# Reference_Design.net
KiCad netlist of a schematic drawn in EAGLE
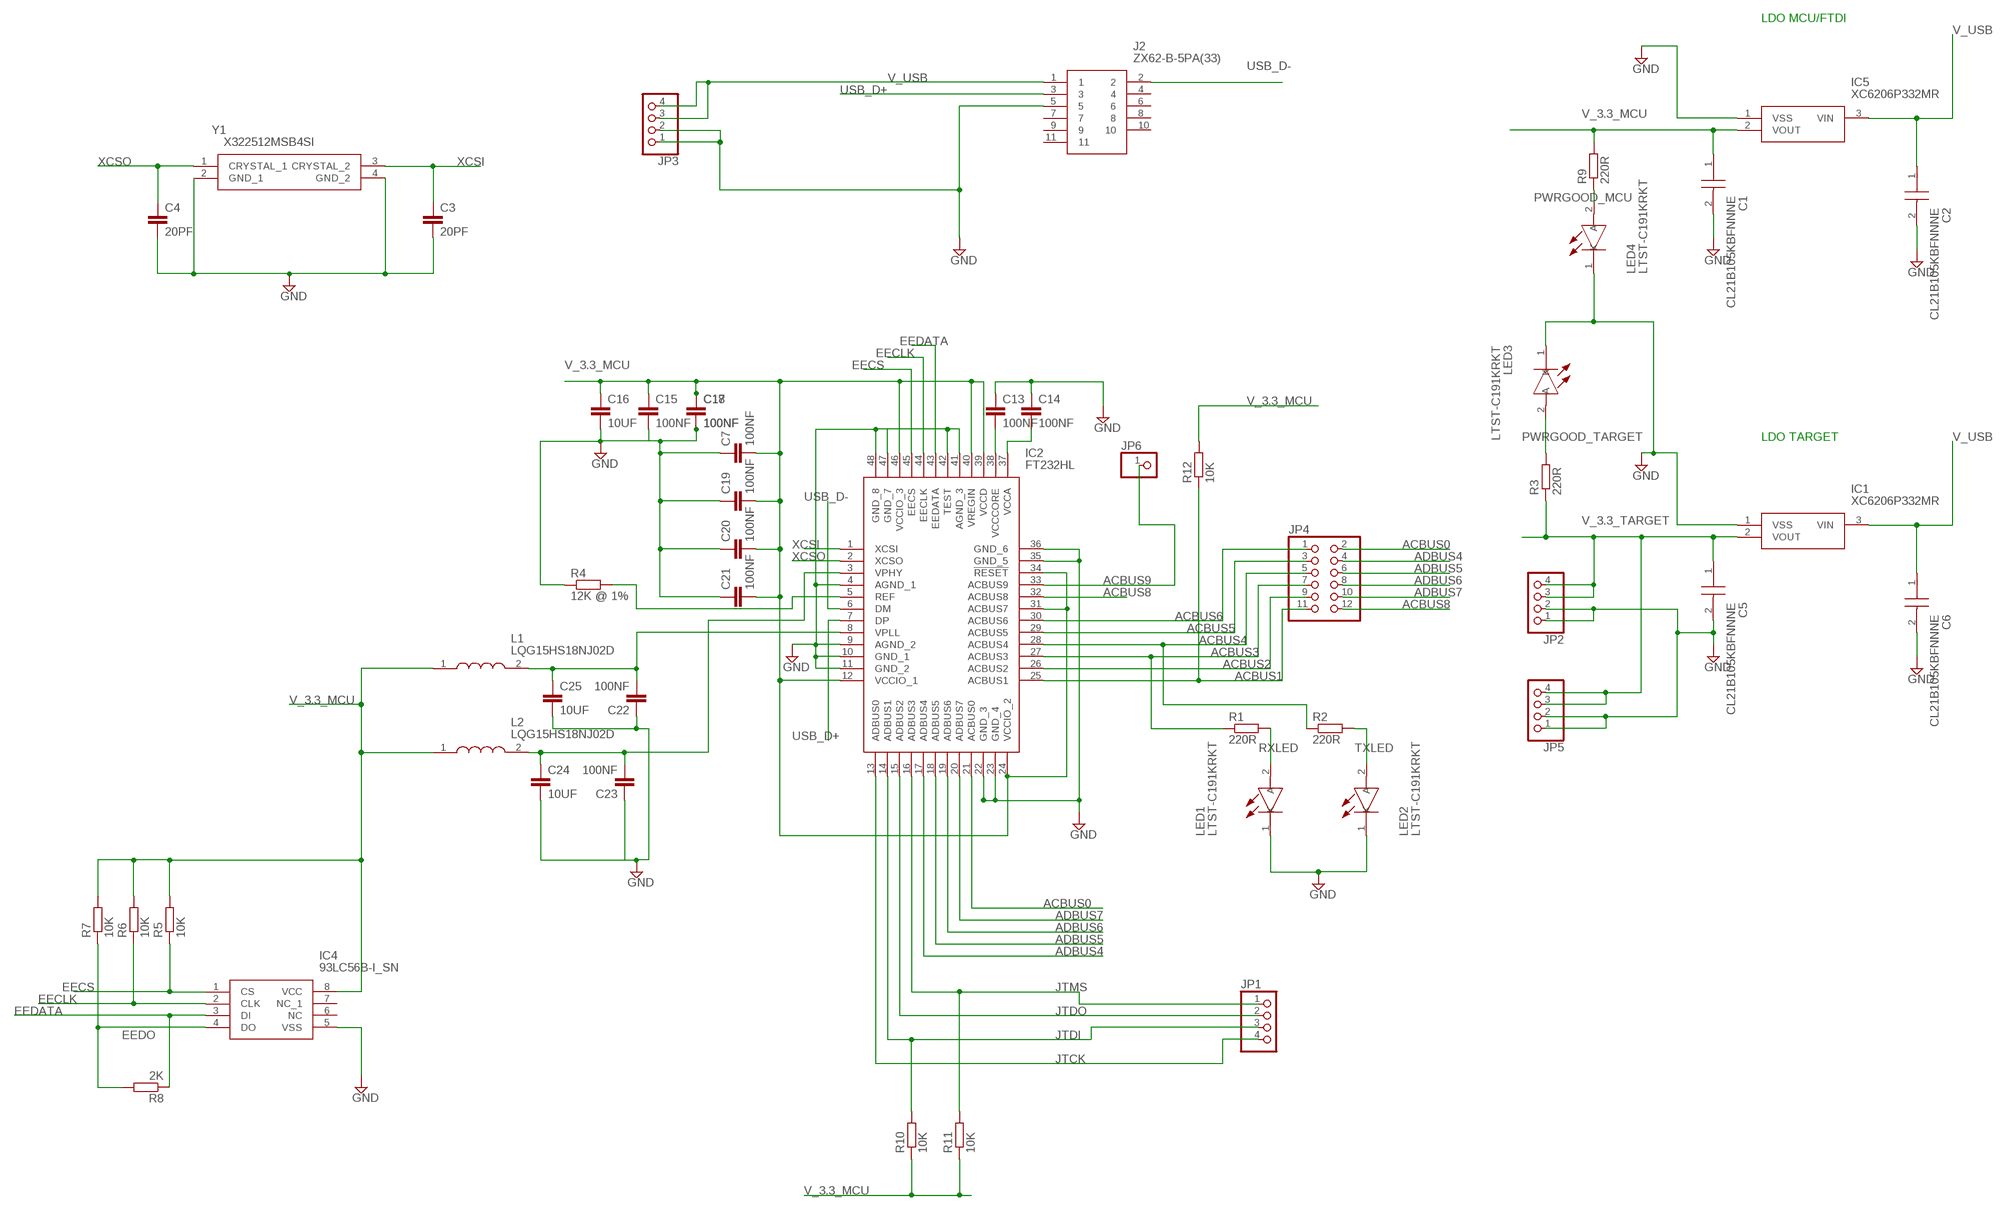
[diagram p0: schematic, sheet 1]

(export (version "E")
  (design (tool "Eeschema 10.0.6"))
  (components
    (comp (ref "C1")
      (value "CL21B105KBFNNNE")
      (footprint "eagle-import:CAPC2012X135N")
      (libsource (lib "eagle-import") (part "CL21B105KBFNNNE"))
    )
    (comp (ref "C2")
      (value "CL21B105KBFNNNE")
      (footprint "eagle-import:CAPC2012X135N")
      (libsource (lib "eagle-import") (part "CL21B105KBFNNNE"))
    )
    (comp (ref "C3")
      (value "20PF")
      (footprint "eagle-import:C0603")
      (libsource (lib "eagle-import") (part "C-EUC0603"))
    )
    (comp (ref "C4")
      (value "20PF")
      (footprint "eagle-import:C0603")
      (libsource (lib "eagle-import") (part "C-EUC0603"))
    )
    (comp (ref "C5")
      (value "CL21B105KBFNNNE")
      (footprint "eagle-import:CAPC2012X135N")
      (libsource (lib "eagle-import") (part "CL21B105KBFNNNE"))
    )
    (comp (ref "C6")
      (value "CL21B105KBFNNNE")
      (footprint "eagle-import:CAPC2012X135N")
      (libsource (lib "eagle-import") (part "CL21B105KBFNNNE"))
    )
    (comp (ref "C7")
      (value "100NF")
      (footprint "eagle-import:C0603")
      (libsource (lib "eagle-import") (part "C-EUC0603"))
    )
    (comp (ref "C13")
      (value "100NF")
      (footprint "eagle-import:C0603")
      (libsource (lib "eagle-import") (part "C-EUC0603"))
    )
    (comp (ref "C14")
      (value "100NF")
      (footprint "eagle-import:C0603")
      (libsource (lib "eagle-import") (part "C-EUC0603"))
    )
    (comp (ref "C15")
      (value "100NF")
      (footprint "eagle-import:C0603")
      (libsource (lib "eagle-import") (part "C-EUC0603"))
    )
    (comp (ref "C16")
      (value "10UF")
      (footprint "eagle-import:C1206")
      (libsource (lib "eagle-import") (part "C-EUC1206"))
    )
    (comp (ref "C17")
      (value "100NF")
      (footprint "eagle-import:C0603")
      (libsource (lib "eagle-import") (part "C-EUC0603"))
    )
    (comp (ref "C18")
      (value "100NF")
      (footprint "eagle-import:C0603")
      (libsource (lib "eagle-import") (part "C-EUC0603"))
    )
    (comp (ref "C19")
      (value "100NF")
      (footprint "eagle-import:C0603")
      (libsource (lib "eagle-import") (part "C-EUC0603"))
    )
    (comp (ref "C20")
      (value "100NF")
      (footprint "eagle-import:C0603")
      (libsource (lib "eagle-import") (part "C-EUC0603"))
    )
    (comp (ref "C21")
      (value "100NF")
      (footprint "eagle-import:C0603")
      (libsource (lib "eagle-import") (part "C-EUC0603"))
    )
    (comp (ref "C22")
      (value "100NF")
      (footprint "eagle-import:C0603")
      (libsource (lib "eagle-import") (part "C-EUC0603"))
    )
    (comp (ref "C23")
      (value "100NF")
      (footprint "eagle-import:C0603")
      (libsource (lib "eagle-import") (part "C-EUC0603"))
    )
    (comp (ref "C24")
      (value "10UF")
      (footprint "eagle-import:C1206")
      (libsource (lib "eagle-import") (part "C-EUC1206"))
    )
    (comp (ref "C25")
      (value "10UF")
      (footprint "eagle-import:C1206")
      (libsource (lib "eagle-import") (part "C-EUC1206"))
    )
    (comp (ref "IC1")
      (value "XC6206P332MR")
      (footprint "eagle-import:SOT95P280X130-3N")
      (libsource (lib "eagle-import") (part "XC6206P332MR"))
    )
    (comp (ref "IC2")
      (value "FT232HL")
      (footprint "eagle-import:QFP50P900X900X160-48N")
      (fields
        (field (name "MANUFACTURER_PART_NUMBER") "FT232HL-REEL")
        (field (name "MOUSER_PART_NUMBER") "895-FT232HL-REEL")
        (field (name "RS_PART_NUMBER") "7377843P")
      )
      (libsource (lib "eagle-import") (part "FT232HL-REEL"))
    )
    (comp (ref "IC4")
      (value "93LC56B-I_SN")
      (footprint "eagle-import:SOIC127P600X175-8N")
      (fields
        (field (name "MANUFACTURER_PART_NUMBER") "93LC56B-I/SN")
        (field (name "MOUSER_PART_NUMBER") "579-93LC56BISN")
        (field (name "RS_PART_NUMBER") "0454347P")
      )
      (libsource (lib "eagle-import") (part "93LC56B-I_SN"))
    )
    (comp (ref "IC5")
      (value "XC6206P332MR")
      (footprint "eagle-import:SOT95P280X130-3N")
      (libsource (lib "eagle-import") (part "XC6206P332MR"))
    )
    (comp (ref "J2")
      (value "ZX62-B-5PA(33)")
      (footprint "eagle-import:ZX62B5PA33")
      (fields
        (field (name "MOUSER_PART_NUMBER") "798-ZX62-B-5PA33")
        (field (name "RS_PART_NUMBER") "1362267")
      )
      (libsource (lib "eagle-import") (part "ZX62-B-5PA(33)"))
    )
    (comp (ref "JP1")
      (value "PINHD-1X4")
      (footprint "eagle-import:1X04")
      (libsource (lib "eagle-import") (part "PINHD-1X4"))
    )
    (comp (ref "JP2")
      (value "PINHD-1X4")
      (footprint "eagle-import:1X04")
      (libsource (lib "eagle-import") (part "PINHD-1X4"))
    )
    (comp (ref "JP3")
      (value "PINHD-1X4")
      (footprint "eagle-import:1X04")
      (libsource (lib "eagle-import") (part "PINHD-1X4"))
    )
    (comp (ref "JP4")
      (value "PINHD-2X6")
      (footprint "eagle-import:2X06")
      (libsource (lib "eagle-import") (part "PINHD-2X6"))
    )
    (comp (ref "JP5")
      (value "PINHD-1X4")
      (footprint "eagle-import:1X04")
      (libsource (lib "eagle-import") (part "PINHD-1X4"))
    )
    (comp (ref "JP6")
      (value "PINHD-1X1")
      (footprint "eagle-import:1X01")
      (libsource (lib "eagle-import") (part "PINHD-1X1"))
    )
    (comp (ref "L1")
      (value "LQG15HS18NJ02D")
      (footprint "eagle-import:INDC1005X55N")
      (fields
        (field (name "MOUSER_PART_NUMBER") "81-LQG15HS18NJ02D")
        (field (name "RS_PART_NUMBER") "7254910")
      )
      (libsource (lib "eagle-import") (part "LQG15HS18NJ02D"))
    )
    (comp (ref "L2")
      (value "LQG15HS18NJ02D")
      (footprint "eagle-import:INDC1005X55N")
      (fields
        (field (name "MOUSER_PART_NUMBER") "81-LQG15HS18NJ02D")
        (field (name "RS_PART_NUMBER") "7254910")
      )
      (libsource (lib "eagle-import") (part "LQG15HS18NJ02D"))
    )
    (comp (ref "LED1")
      (value "LTST-C191KRKT")
      (footprint "eagle-import:LEDC1608X55N")
      (fields
        (field (name "MOUSER_PART_NUMBER") "859-LTST-C191KRKT")
        (field (name "RS_PART_NUMBER") "1278415P")
      )
      (libsource (lib "eagle-import") (part "LTST-C191KRKT"))
    )
    (comp (ref "LED2")
      (value "LTST-C191KRKT")
      (footprint "eagle-import:LEDC1608X55N")
      (fields
        (field (name "MOUSER_PART_NUMBER") "859-LTST-C191KRKT")
        (field (name "RS_PART_NUMBER") "1278415P")
      )
      (libsource (lib "eagle-import") (part "LTST-C191KRKT"))
    )
    (comp (ref "LED3")
      (value "LTST-C191KRKT")
      (footprint "eagle-import:LEDC1608X55N")
      (fields
        (field (name "MOUSER_PART_NUMBER") "859-LTST-C191KRKT")
        (field (name "RS_PART_NUMBER") "1278415P")
      )
      (libsource (lib "eagle-import") (part "LTST-C191KRKT"))
    )
    (comp (ref "LED4")
      (value "LTST-C191KRKT")
      (footprint "eagle-import:LEDC1608X55N")
      (fields
        (field (name "MOUSER_PART_NUMBER") "859-LTST-C191KRKT")
        (field (name "RS_PART_NUMBER") "1278415P")
      )
      (libsource (lib "eagle-import") (part "LTST-C191KRKT"))
    )
    (comp (ref "R1")
      (value "220R")
      (footprint "eagle-import:R0603")
      (libsource (lib "eagle-import") (part "R-EU_R0603"))
    )
    (comp (ref "R2")
      (value "220R")
      (footprint "eagle-import:R0603")
      (libsource (lib "eagle-import") (part "R-EU_R0603"))
    )
    (comp (ref "R3")
      (value "220R")
      (footprint "eagle-import:R0603")
      (libsource (lib "eagle-import") (part "R-EU_R0603"))
    )
    (comp (ref "R4")
      (value "12K @ 1%")
      (footprint "eagle-import:R0603")
      (libsource (lib "eagle-import") (part "R-EU_R0603"))
    )
    (comp (ref "R5")
      (value "10K")
      (footprint "eagle-import:R1206")
      (libsource (lib "eagle-import") (part "R-EU_R1206"))
    )
    (comp (ref "R6")
      (value "10K")
      (footprint "eagle-import:R1206")
      (libsource (lib "eagle-import") (part "R-EU_R1206"))
    )
    (comp (ref "R7")
      (value "10K")
      (footprint "eagle-import:R1206")
      (libsource (lib "eagle-import") (part "R-EU_R1206"))
    )
    (comp (ref "R8")
      (value "2K")
      (footprint "eagle-import:R1206")
      (libsource (lib "eagle-import") (part "R-EU_R1206"))
    )
    (comp (ref "R9")
      (value "220R")
      (footprint "eagle-import:R0603")
      (libsource (lib "eagle-import") (part "R-EU_R0603"))
    )
    (comp (ref "R10")
      (value "10K")
      (footprint "eagle-import:R1206")
      (libsource (lib "eagle-import") (part "R-EU_R1206"))
    )
    (comp (ref "R11")
      (value "10K")
      (footprint "eagle-import:R1206")
      (libsource (lib "eagle-import") (part "R-EU_R1206"))
    )
    (comp (ref "R12")
      (value "10K")
      (footprint "eagle-import:R1206")
      (libsource (lib "eagle-import") (part "R-EU_R1206"))
    )
    (comp (ref "Y1")
      (value "X322512MSB4SI")
      (footprint "eagle-import:X322512MSB4SI")
      (libsource (lib "eagle-import") (part "X322512MSB4SI"))
    )
  )
  (nets
    (net (code "1") (name "/ACBUS0") (class "Default")
      (node (ref "IC2") (pin "21") (pinfunction "ACBUS0_21") (pintype "bidirectional"))
      (node (ref "JP4") (pin "2") (pinfunction "2_2") (pintype "passive"))
    )
    (net (code "2") (name "/ACBUS1") (class "Default")
      (node (ref "IC2") (pin "25") (pinfunction "ACBUS1_25") (pintype "bidirectional"))
      (node (ref "JP4") (pin "11") (pinfunction "11_11") (pintype "passive"))
      (node (ref "R12") (pin "1") (pinfunction "1_1") (pintype "passive"))
    )
    (net (code "3") (name "/ACBUS2") (class "Default")
      (node (ref "IC2") (pin "26") (pinfunction "ACBUS2_26") (pintype "bidirectional"))
      (node (ref "JP4") (pin "9") (pinfunction "9_9") (pintype "passive"))
    )
    (net (code "4") (name "/ACBUS3") (class "Default")
      (node (ref "IC2") (pin "27") (pinfunction "ACBUS3_27") (pintype "bidirectional"))
      (node (ref "JP4") (pin "7") (pinfunction "7_7") (pintype "passive"))
      (node (ref "R1") (pin "1") (pinfunction "1_1") (pintype "passive"))
    )
    (net (code "5") (name "/ACBUS4") (class "Default")
      (node (ref "IC2") (pin "28") (pinfunction "ACBUS4_28") (pintype "bidirectional"))
      (node (ref "JP4") (pin "5") (pinfunction "5_5") (pintype "passive"))
      (node (ref "R2") (pin "1") (pinfunction "1_1") (pintype "passive"))
    )
    (net (code "6") (name "/ACBUS5") (class "Default")
      (node (ref "IC2") (pin "29") (pinfunction "ACBUS5_29") (pintype "bidirectional"))
      (node (ref "JP4") (pin "3") (pinfunction "3_3") (pintype "passive"))
    )
    (net (code "7") (name "/ACBUS6") (class "Default")
      (node (ref "IC2") (pin "30") (pinfunction "ACBUS6_30") (pintype "bidirectional"))
      (node (ref "JP4") (pin "1") (pinfunction "1_1") (pintype "passive"))
    )
    (net (code "8") (name "/ACBUS8") (class "Default")
      (node (ref "IC2") (pin "32") (pinfunction "ACBUS8_32") (pintype "bidirectional"))
      (node (ref "JP4") (pin "12") (pinfunction "12_12") (pintype "passive"))
    )
    (net (code "9") (name "/ACBUS9") (class "Default")
      (node (ref "IC2") (pin "33") (pinfunction "ACBUS9_33") (pintype "bidirectional"))
      (node (ref "JP6") (pin "1") (pinfunction "1_1") (pintype "passive"))
    )
    (net (code "10") (name "/ADBUS4") (class "Default")
      (node (ref "IC2") (pin "17") (pinfunction "ADBUS4_17") (pintype "bidirectional"))
      (node (ref "JP4") (pin "4") (pinfunction "4_4") (pintype "passive"))
    )
    (net (code "11") (name "/ADBUS5") (class "Default")
      (node (ref "IC2") (pin "18") (pinfunction "ADBUS5_18") (pintype "bidirectional"))
      (node (ref "JP4") (pin "6") (pinfunction "6_6") (pintype "passive"))
    )
    (net (code "12") (name "/ADBUS6") (class "Default")
      (node (ref "IC2") (pin "19") (pinfunction "ADBUS6_19") (pintype "bidirectional"))
      (node (ref "JP4") (pin "8") (pinfunction "8_8") (pintype "passive"))
    )
    (net (code "13") (name "/ADBUS7") (class "Default")
      (node (ref "IC2") (pin "20") (pinfunction "ADBUS7_20") (pintype "bidirectional"))
      (node (ref "JP4") (pin "10") (pinfunction "10_10") (pintype "passive"))
    )
    (net (code "14") (name "/EECLK") (class "Default")
      (node (ref "IC2") (pin "44") (pinfunction "EECLK_44") (pintype "input"))
      (node (ref "IC4") (pin "2") (pinfunction "CLK_2") (pintype "input"))
      (node (ref "R6") (pin "1") (pinfunction "1_1") (pintype "passive"))
    )
    (net (code "15") (name "/EECS") (class "Default")
      (node (ref "IC2") (pin "45") (pinfunction "EECS_45") (pintype "input"))
      (node (ref "IC4") (pin "1") (pinfunction "CS_1") (pintype "input"))
      (node (ref "R5") (pin "1") (pinfunction "1_1") (pintype "passive"))
    )
    (net (code "16") (name "/EEDATA") (class "Default")
      (node (ref "IC2") (pin "43") (pinfunction "EEDATA_43") (pintype "bidirectional"))
      (node (ref "IC4") (pin "3") (pinfunction "DI_3") (pintype "bidirectional"))
      (node (ref "R8") (pin "1") (pinfunction "1_1") (pintype "passive"))
    )
    (net (code "17") (name "/EEDO") (class "Default")
      (node (ref "IC4") (pin "4") (pinfunction "DO_4") (pintype "bidirectional"))
      (node (ref "R7") (pin "1") (pinfunction "1_1") (pintype "passive"))
      (node (ref "R8") (pin "2") (pinfunction "2_2") (pintype "passive"))
    )
    (net (code "18") (name "/JTCK") (class "Default")
      (node (ref "IC2") (pin "13") (pinfunction "ADBUS0_13") (pintype "bidirectional"))
      (node (ref "JP1") (pin "4") (pinfunction "4_4") (pintype "passive"))
    )
    (net (code "19") (name "/JTDI") (class "Default")
      (node (ref "IC2") (pin "14") (pinfunction "ADBUS1_14") (pintype "bidirectional"))
      (node (ref "JP1") (pin "3") (pinfunction "3_3") (pintype "passive"))
      (node (ref "R10") (pin "2") (pinfunction "2_2") (pintype "passive"))
    )
    (net (code "20") (name "/JTDO") (class "Default")
      (node (ref "IC2") (pin "15") (pinfunction "ADBUS2_15") (pintype "bidirectional"))
      (node (ref "JP1") (pin "2") (pinfunction "2_2") (pintype "passive"))
    )
    (net (code "21") (name "/JTMS") (class "Default")
      (node (ref "IC2") (pin "16") (pinfunction "ADBUS3_16") (pintype "bidirectional"))
      (node (ref "JP1") (pin "1") (pinfunction "1_1") (pintype "passive"))
      (node (ref "R11") (pin "2") (pinfunction "2_2") (pintype "passive"))
    )
    (net (code "22") (name "/PWRGOOD_MCU") (class "Default")
      (node (ref "LED4") (pin "2") (pinfunction "A_2") (pintype "bidirectional"))
      (node (ref "R9") (pin "1") (pinfunction "1_1") (pintype "passive"))
    )
    (net (code "23") (name "/PWRGOOD_TARGET") (class "Default")
      (node (ref "LED3") (pin "2") (pinfunction "A_2") (pintype "bidirectional"))
      (node (ref "R3") (pin "2") (pinfunction "2_2") (pintype "passive"))
    )
    (net (code "24") (name "/RXLED") (class "Default")
      (node (ref "LED1") (pin "2") (pinfunction "A_2") (pintype "bidirectional"))
      (node (ref "R1") (pin "2") (pinfunction "2_2") (pintype "passive"))
    )
    (net (code "25") (name "/TXLED") (class "Default")
      (node (ref "LED2") (pin "2") (pinfunction "A_2") (pintype "bidirectional"))
      (node (ref "R2") (pin "2") (pinfunction "2_2") (pintype "passive"))
    )
    (net (code "26") (name "/USB_D+") (class "Default")
      (node (ref "IC2") (pin "7") (pinfunction "DP_7") (pintype "bidirectional"))
      (node (ref "J2") (pin "3") (pinfunction "3_3") (pintype "bidirectional"))
    )
    (net (code "27") (name "/USB_D-") (class "Default")
      (node (ref "IC2") (pin "6") (pinfunction "DM_6") (pintype "bidirectional"))
      (node (ref "J2") (pin "2") (pinfunction "2_2") (pintype "bidirectional"))
    )
    (net (code "28") (name "/V_3.3_MCU") (class "Default")
      (node (ref "C1") (pin "1") (pinfunction "1_1") (pintype "bidirectional"))
      (node (ref "C15") (pin "1") (pinfunction "1_1") (pintype "passive"))
      (node (ref "C16") (pin "1") (pinfunction "1_1") (pintype "passive"))
      (node (ref "C17") (pin "1") (pinfunction "1_1") (pintype "passive"))
      (node (ref "C18") (pin "1") (pinfunction "1_1") (pintype "passive"))
      (node (ref "C19") (pin "2") (pinfunction "2_2") (pintype "passive"))
      (node (ref "C20") (pin "2") (pinfunction "2_2") (pintype "passive"))
      (node (ref "C21") (pin "2") (pinfunction "2_2") (pintype "passive"))
      (node (ref "C7") (pin "2") (pinfunction "2_2") (pintype "passive"))
      (node (ref "IC2") (pin "12") (pinfunction "VCCIO_1_12") (pintype "power_in"))
      (node (ref "IC2") (pin "24") (pinfunction "VCCIO_2_24") (pintype "power_in"))
      (node (ref "IC2") (pin "31") (pinfunction "ACBUS7_31") (pintype "bidirectional"))
      (node (ref "IC2") (pin "34") (pinfunction "~{RESET}_34") (pintype "bidirectional"))
      (node (ref "IC2") (pin "39") (pinfunction "VCCD_39") (pintype "power_in"))
      (node (ref "IC2") (pin "40") (pinfunction "VREGIN_40") (pintype "input"))
      (node (ref "IC2") (pin "46") (pinfunction "VCCIO_3_46") (pintype "power_in"))
      (node (ref "IC4") (pin "8") (pinfunction "VCC_8") (pintype "power_in"))
      (node (ref "IC5") (pin "2") (pinfunction "VOUT_2") (pintype "output"))
      (node (ref "L1") (pin "1") (pinfunction "1_1") (pintype "bidirectional"))
      (node (ref "L2") (pin "1") (pinfunction "1_1") (pintype "bidirectional"))
      (node (ref "R10") (pin "1") (pinfunction "1_1") (pintype "passive"))
      (node (ref "R11") (pin "1") (pinfunction "1_1") (pintype "passive"))
      (node (ref "R12") (pin "2") (pinfunction "2_2") (pintype "passive"))
      (node (ref "R5") (pin "2") (pinfunction "2_2") (pintype "passive"))
      (node (ref "R6") (pin "2") (pinfunction "2_2") (pintype "passive"))
      (node (ref "R7") (pin "2") (pinfunction "2_2") (pintype "passive"))
      (node (ref "R9") (pin "2") (pinfunction "2_2") (pintype "passive"))
    )
    (net (code "29") (name "/V_3.3_TARGET") (class "Default")
      (node (ref "C5") (pin "1") (pinfunction "1_1") (pintype "bidirectional"))
      (node (ref "IC1") (pin "2") (pinfunction "VOUT_2") (pintype "output"))
      (node (ref "JP2") (pin "3") (pinfunction "3_3") (pintype "passive"))
      (node (ref "JP2") (pin "4") (pinfunction "4_4") (pintype "passive"))
      (node (ref "JP5") (pin "3") (pinfunction "3_3") (pintype "passive"))
      (node (ref "JP5") (pin "4") (pinfunction "4_4") (pintype "passive"))
      (node (ref "R3") (pin "1") (pinfunction "1_1") (pintype "passive"))
    )
    (net (code "30") (name "/V_USB") (class "Default")
      (node (ref "C2") (pin "1") (pinfunction "1_1") (pintype "bidirectional"))
      (node (ref "C6") (pin "1") (pinfunction "1_1") (pintype "bidirectional"))
      (node (ref "IC1") (pin "3") (pinfunction "VIN_3") (pintype "input"))
      (node (ref "IC5") (pin "3") (pinfunction "VIN_3") (pintype "input"))
      (node (ref "J2") (pin "1") (pinfunction "1_1") (pintype "bidirectional"))
      (node (ref "JP3") (pin "3") (pinfunction "3_3") (pintype "passive"))
      (node (ref "JP3") (pin "4") (pinfunction "4_4") (pintype "passive"))
    )
    (net (code "31") (name "/XCSI") (class "Default")
      (node (ref "C3") (pin "1") (pinfunction "1_1") (pintype "passive"))
      (node (ref "IC2") (pin "1") (pinfunction "XCSI_1") (pintype "input"))
      (node (ref "Y1") (pin "3") (pinfunction "CRYSTAL_2_3") (pintype "bidirectional"))
    )
    (net (code "32") (name "/XCSO") (class "Default")
      (node (ref "C4") (pin "1") (pinfunction "1_1") (pintype "passive"))
      (node (ref "IC2") (pin "2") (pinfunction "XCSO_2") (pintype "input"))
      (node (ref "Y1") (pin "1") (pinfunction "CRYSTAL_1_1") (pintype "bidirectional"))
    )
    (net (code "33") (name "GND") (class "Default")
      (node (ref "C1") (pin "2") (pinfunction "2_2") (pintype "bidirectional"))
      (node (ref "C13") (pin "1") (pinfunction "1_1") (pintype "passive"))
      (node (ref "C14") (pin "1") (pinfunction "1_1") (pintype "passive"))
      (node (ref "C15") (pin "2") (pinfunction "2_2") (pintype "passive"))
      (node (ref "C16") (pin "2") (pinfunction "2_2") (pintype "passive"))
      (node (ref "C17") (pin "2") (pinfunction "2_2") (pintype "passive"))
      (node (ref "C18") (pin "2") (pinfunction "2_2") (pintype "passive"))
      (node (ref "C19") (pin "1") (pinfunction "1_1") (pintype "passive"))
      (node (ref "C2") (pin "2") (pinfunction "2_2") (pintype "bidirectional"))
      (node (ref "C20") (pin "1") (pinfunction "1_1") (pintype "passive"))
      (node (ref "C21") (pin "1") (pinfunction "1_1") (pintype "passive"))
      (node (ref "C22") (pin "1") (pinfunction "1_1") (pintype "passive"))
      (node (ref "C23") (pin "1") (pinfunction "1_1") (pintype "passive"))
      (node (ref "C24") (pin "2") (pinfunction "2_2") (pintype "passive"))
      (node (ref "C25") (pin "2") (pinfunction "2_2") (pintype "passive"))
      (node (ref "C3") (pin "2") (pinfunction "2_2") (pintype "passive"))
      (node (ref "C4") (pin "2") (pinfunction "2_2") (pintype "passive"))
      (node (ref "C5") (pin "2") (pinfunction "2_2") (pintype "bidirectional"))
      (node (ref "C6") (pin "2") (pinfunction "2_2") (pintype "bidirectional"))
      (node (ref "C7") (pin "1") (pinfunction "1_1") (pintype "passive"))
      (node (ref "IC1") (pin "1") (pinfunction "VSS_1") (pintype "power_in"))
      (node (ref "IC2") (pin "10") (pinfunction "GND_1_10") (pintype "power_in"))
      (node (ref "IC2") (pin "11") (pinfunction "GND_2_11") (pintype "power_in"))
      (node (ref "IC2") (pin "22") (pinfunction "GND_3_22") (pintype "power_in"))
      (node (ref "IC2") (pin "23") (pinfunction "GND_4_23") (pintype "power_in"))
      (node (ref "IC2") (pin "35") (pinfunction "GND_5_35") (pintype "power_in"))
      (node (ref "IC2") (pin "36") (pinfunction "GND_6_36") (pintype "power_in"))
      (node (ref "IC2") (pin "4") (pinfunction "AGND_1_4") (pintype "power_in"))
      (node (ref "IC2") (pin "41") (pinfunction "AGND_3_41") (pintype "power_in"))
      (node (ref "IC2") (pin "42") (pinfunction "TEST_42") (pintype "bidirectional"))
      (node (ref "IC2") (pin "47") (pinfunction "GND_7_47") (pintype "power_in"))
      (node (ref "IC2") (pin "48") (pinfunction "GND_8_48") (pintype "power_in"))
      (node (ref "IC2") (pin "9") (pinfunction "AGND_2_9") (pintype "power_in"))
      (node (ref "IC4") (pin "5") (pinfunction "VSS_5") (pintype "power_in"))
      (node (ref "IC5") (pin "1") (pinfunction "VSS_1") (pintype "power_in"))
      (node (ref "J2") (pin "5") (pinfunction "5_5") (pintype "bidirectional"))
      (node (ref "JP2") (pin "1") (pinfunction "1_1") (pintype "passive"))
      (node (ref "JP2") (pin "2") (pinfunction "2_2") (pintype "passive"))
      (node (ref "JP3") (pin "1") (pinfunction "1_1") (pintype "passive"))
      (node (ref "JP3") (pin "2") (pinfunction "2_2") (pintype "passive"))
      (node (ref "JP5") (pin "1") (pinfunction "1_1") (pintype "passive"))
      (node (ref "JP5") (pin "2") (pinfunction "2_2") (pintype "passive"))
      (node (ref "LED1") (pin "1") (pinfunction "K_1") (pintype "bidirectional"))
      (node (ref "LED2") (pin "1") (pinfunction "K_1") (pintype "bidirectional"))
      (node (ref "LED3") (pin "1") (pinfunction "K_1") (pintype "bidirectional"))
      (node (ref "LED4") (pin "1") (pinfunction "K_1") (pintype "bidirectional"))
      (node (ref "R4") (pin "1") (pinfunction "1_1") (pintype "passive"))
      (node (ref "Y1") (pin "2") (pinfunction "GND_1_2") (pintype "bidirectional"))
      (node (ref "Y1") (pin "4") (pinfunction "GND_2_4") (pintype "bidirectional"))
    )
    (net (code "34") (name "Net-(IC2-REF)") (class "Default")
      (node (ref "IC2") (pin "5") (pinfunction "REF_5") (pintype "input"))
      (node (ref "R4") (pin "2") (pinfunction "2_2") (pintype "passive"))
    )
    (net (code "35") (name "Net-(IC2-VCCA)") (class "Default")
      (node (ref "C14") (pin "2") (pinfunction "2_2") (pintype "passive"))
      (node (ref "IC2") (pin "37") (pinfunction "VCCA_37") (pintype "power_in"))
    )
    (net (code "36") (name "Net-(IC2-VCCCORE)") (class "Default")
      (node (ref "C13") (pin "2") (pinfunction "2_2") (pintype "passive"))
      (node (ref "IC2") (pin "38") (pinfunction "VCCCORE_38") (pintype "power_in"))
    )
    (net (code "37") (name "Net-(IC2-VPHY)") (class "Default")
      (node (ref "C23") (pin "2") (pinfunction "2_2") (pintype "passive"))
      (node (ref "C24") (pin "1") (pinfunction "1_1") (pintype "passive"))
      (node (ref "IC2") (pin "3") (pinfunction "VPHY_3") (pintype "bidirectional"))
      (node (ref "L2") (pin "2") (pinfunction "2_2") (pintype "bidirectional"))
    )
    (net (code "38") (name "Net-(IC2-VPLL)") (class "Default")
      (node (ref "C22") (pin "2") (pinfunction "2_2") (pintype "passive"))
      (node (ref "C25") (pin "1") (pinfunction "1_1") (pintype "passive"))
      (node (ref "IC2") (pin "8") (pinfunction "VPLL_8") (pintype "bidirectional"))
      (node (ref "L1") (pin "2") (pinfunction "2_2") (pintype "bidirectional"))
    )
    (net (code "39") (name "unconnected-(IC4-NC-Pad6)") (class "Default")
      (node (ref "IC4") (pin "6") (pinfunction "NC_6") (pintype "no_connect"))
    )
    (net (code "40") (name "unconnected-(IC4-NC_1-Pad7)") (class "Default")
      (node (ref "IC4") (pin "7") (pinfunction "NC_1_7") (pintype "bidirectional"))
    )
    (net (code "41") (name "unconnected-(J2-Pad4)") (class "Default")
      (node (ref "J2") (pin "4") (pinfunction "4_4") (pintype "bidirectional"))
    )
    (net (code "42") (name "unconnected-(J2-Pad6)") (class "Default")
      (node (ref "J2") (pin "6") (pinfunction "6_6") (pintype "bidirectional"))
    )
    (net (code "43") (name "unconnected-(J2-Pad7)") (class "Default")
      (node (ref "J2") (pin "7") (pinfunction "7_7") (pintype "bidirectional"))
    )
    (net (code "44") (name "unconnected-(J2-Pad8)") (class "Default")
      (node (ref "J2") (pin "8") (pinfunction "8_8") (pintype "bidirectional"))
    )
    (net (code "45") (name "unconnected-(J2-Pad9)") (class "Default")
      (node (ref "J2") (pin "9") (pinfunction "9_9") (pintype "bidirectional"))
    )
    (net (code "46") (name "unconnected-(J2-Pad10)") (class "Default")
      (node (ref "J2") (pin "10") (pinfunction "10_10") (pintype "bidirectional"))
    )
    (net (code "47") (name "unconnected-(J2-Pad11)") (class "Default")
      (node (ref "J2") (pin "11") (pinfunction "11_11") (pintype "bidirectional"))
    )
  )
)
